# Sheet1.net
KiCad netlist of a schematic drawn in Altium Designer
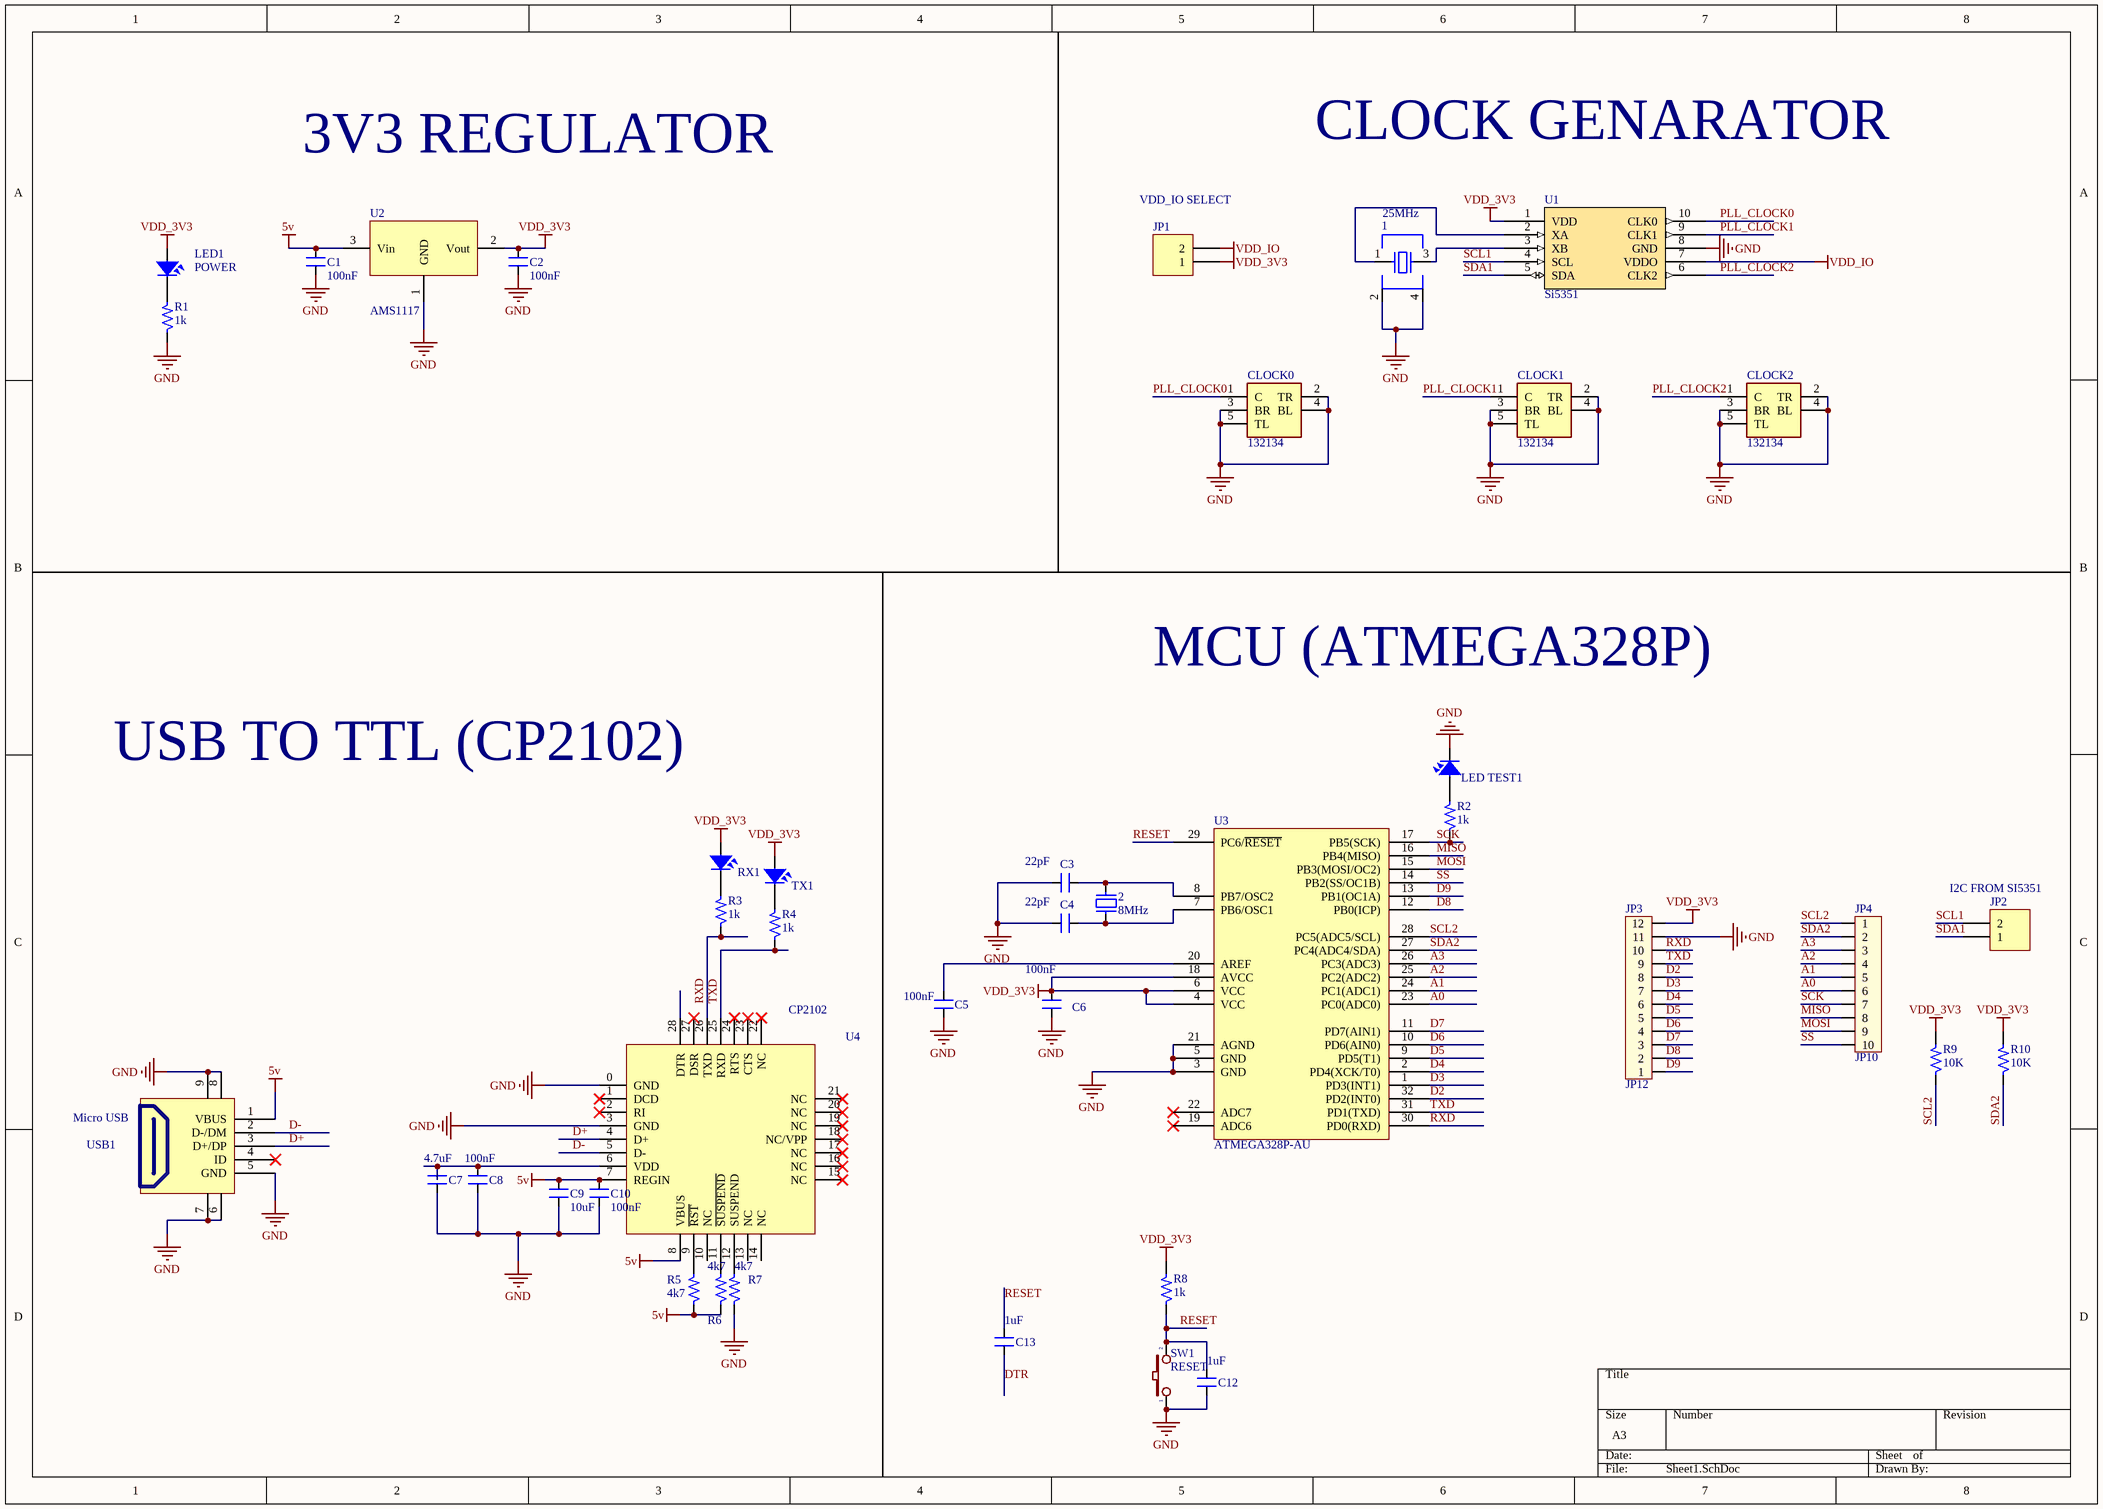
[diagram p0: Sheet1.SchDoc]

(export (version "E")
  (design (tool "Eeschema 10.0.6"))
  (components
    (comp (ref "1")
      (value "25MHz")
      (footprint "XT4-3.2x2.5")
      (description "4 pin crystal surface mount")
      (libsource (lib "HaiThai") (part "XT4_SMD"))
    )
    (comp (ref "2")
      (value "8MHz")
      (footprint "XT 5032")
      (description "Crystal 455kHz Infrared")
      (libsource (lib "HaiThai") (part "XT455k"))
    )
    (comp (ref "C1")
      (value "100nF")
      (footprint "0603_cap")
      (description "Cap np W0.4")
      (libsource (lib "HaiThai") (part "CN4"))
    )
    (comp (ref "C2")
      (value "100nF")
      (footprint "0603_cap")
      (description "Cap np W0.4")
      (libsource (lib "HaiThai") (part "CN4"))
    )
    (comp (ref "C3")
      (value "22pF")
      (footprint "0603_cap")
      (description "Cap np W0.4")
      (libsource (lib "HaiThai") (part "CN4"))
    )
    (comp (ref "C4")
      (value "22pF")
      (footprint "0603_cap")
      (description "Cap np W0.4")
      (libsource (lib "HaiThai") (part "CN4"))
    )
    (comp (ref "C5")
      (value "100nF")
      (footprint "0603_cap")
      (description "Cap np W0.4")
      (libsource (lib "HaiThai") (part "CN4"))
    )
    (comp (ref "C6")
      (value "100nF")
      (footprint "0603_cap")
      (description "Cap np W0.4")
      (libsource (lib "HaiThai") (part "CN4"))
    )
    (comp (ref "C7")
      (value "100nF")
      (footprint "0603_cap")
      (description "Cap np W0.4")
      (libsource (lib "HaiThai") (part "CN4"))
    )
    (comp (ref "C8")
      (value "4.7uF")
      (footprint "0603_cap")
      (description "Cap np W0.4")
      (libsource (lib "HaiThai") (part "CN4"))
    )
    (comp (ref "C9")
      (value "10uF")
      (footprint "0603_cap")
      (description "Cap np W0.4")
      (libsource (lib "HaiThai") (part "CN4"))
    )
    (comp (ref "C10")
      (value "100nF")
      (footprint "0603_cap")
      (description "Cap np W0.4")
      (libsource (lib "HaiThai") (part "CN4"))
    )
    (comp (ref "C12")
      (value "1uF")
      (footprint "0603_cap")
      (description "Cap np W0.4")
      (libsource (lib "HaiThai") (part "CN4"))
    )
    (comp (ref "C13")
      (value "1uF")
      (footprint "0603_cap")
      (description "Cap np W0.4")
      (libsource (lib "HaiThai") (part "CN4"))
    )
    (comp (ref "CLOCK0")
      (value "132134")
      (footprint "SMA-132322")
      (description "SMA Connector - STRAIGHT JACK FOR P.C. BOARD - Female")
      (libsource (lib "HaiThai") (part "132134"))
    )
    (comp (ref "CLOCK1")
      (value "132134")
      (footprint "SMA-132322")
      (description "SMA Connector - STRAIGHT JACK FOR P.C. BOARD - Female")
      (libsource (lib "HaiThai") (part "132134"))
    )
    (comp (ref "CLOCK2")
      (value "132134")
      (footprint "SMA-132322")
      (description "SMA Connector - STRAIGHT JACK FOR P.C. BOARD - Female")
      (libsource (lib "HaiThai") (part "132134"))
    )
    (comp (ref "JP1")
      (value "Header 2")
      (footprint "JP2-D1T")
      (description "Header, 2-Pin")
      (fields (field (name "MANUFACTURER") "Generic Components"))
      (libsource (lib "") (part "Header 2_1"))
    )
    (comp (ref "JP2")
      (value "Header 2")
      (footprint "JP2-D1T")
      (description "Header, 2-Pin")
      (fields (field (name "MANUFACTURER") "Generic Components"))
      (libsource (lib "HaiThai") (part "Header 2"))
    )
    (comp (ref "JP3")
      (value "JP12")
      (footprint "JP12-D1T")
      (description "Connector 12")
      (libsource (lib "HaiThai") (part "Con12"))
    )
    (comp (ref "JP4")
      (value "JP10")
      (footprint "JP10-D1T")
      (description "Connector 10")
      (libsource (lib "HaiThai") (part "Con10"))
    )
    (comp (ref "LED TEST1")
      (value "LED SMD")
      (footprint "0603_LED")
      (libsource (lib "HaiThai") (part "LED-SMD-0603"))
    )
    (comp (ref "LED1")
      (value "POWER")
      (footprint "0603_LED")
      (libsource (lib "HaiThai") (part "LED-SMD-0603"))
    )
    (comp (ref "R1")
      (value "1k")
      (footprint "0603_res")
      (description "Resistor 1/4W")
      (libsource (lib "HaiThai") (part "R"))
    )
    (comp (ref "R2")
      (value "1k")
      (footprint "0603_res")
      (description "Resistor 1/4W")
      (libsource (lib "HaiThai") (part "R"))
    )
    (comp (ref "R3")
      (value "1k")
      (footprint "0603_res")
      (description "Resistor 1/4W")
      (libsource (lib "HaiThai") (part "R"))
    )
    (comp (ref "R4")
      (value "1k")
      (footprint "0603_res")
      (description "Resistor 1/4W")
      (libsource (lib "HaiThai") (part "R"))
    )
    (comp (ref "R5")
      (value "4k7")
      (footprint "0603_res")
      (description "Resistor 1/4W")
      (libsource (lib "HaiThai") (part "R"))
    )
    (comp (ref "R6")
      (value "4k7")
      (footprint "0603_res")
      (description "Resistor 1/4W")
      (libsource (lib "HaiThai") (part "R"))
    )
    (comp (ref "R7")
      (value "4k7")
      (footprint "0603_res")
      (description "Resistor 1/4W")
      (libsource (lib "HaiThai") (part "R"))
    )
    (comp (ref "R8")
      (value "1k")
      (footprint "0603_res")
      (description "Resistor 1/4W")
      (libsource (lib "HaiThai") (part "R"))
    )
    (comp (ref "R9")
      (value "10K")
      (footprint "0603_res")
      (description "Resistor 1/4W")
      (libsource (lib "HaiThai") (part "R"))
    )
    (comp (ref "R10")
      (value "10K")
      (footprint "0603_res")
      (description "Resistor 1/4W")
      (libsource (lib "HaiThai") (part "R"))
    )
    (comp (ref "RX1")
      (value "LED SMD")
      (footprint "0603_LED")
      (libsource (lib "HaiThai") (part "LED-SMD-0603"))
    )
    (comp (ref "SW1")
      (value "RESET")
      (footprint "SW-SMD")
      (description "Switch button 2 pin")
      (libsource (lib "HaiThai") (part "SW2"))
    )
    (comp (ref "TX1")
      (value "LED SMD")
      (footprint "0603_LED")
      (libsource (lib "HaiThai") (part "LED-SMD-0603"))
    )
    (comp (ref "U1")
      (value "Si5351")
      (footprint "MSOP10_L")
      (description "I2C-PROGRAMMABLE ANY-FREQUENCY CMOS CLOCK")
      (libsource (lib "HaiThai") (part "Si5351"))
    )
    (comp (ref "U2") (value "AMS1117") (footprint "SOT223_N") (libsource (lib "HaiThai") (part "AMS1117")))
    (comp (ref "U3")
      (value "ATMEGA328P-AU")
      (footprint "QFP7X7-G32/X.45N")
      (description "8-bit AVR Microcontrollers")
      (libsource (lib "HaiThai") (part "ATMEGA328P-AU"))
    )
    (comp (ref "U4")
      (value "CP2102")
      (footprint "QFN28 - 9")
      (description "SINGLE-CHIP USB-TO-UART BRIDGE")
      (libsource (lib "HaiThai") (part "CP2102"))
    )
    (comp (ref "USB1")
      (value "Micro USB")
      (footprint "MICROUSB - v2")
      (libsource (lib "HaiThai") (part "USB Micro"))
    )
  )
  (nets
    (net (code "1") (name "/A0") (class "Default")
      (node (ref "JP4") (pin "6") (pinfunction "6_6") (pintype "passive"))
      (node (ref "U3") (pin "23") (pinfunction "PC0(ADC0)_23") (pintype "passive"))
    )
    (net (code "2") (name "/A1") (class "Default")
      (node (ref "JP4") (pin "5") (pinfunction "5_5") (pintype "passive"))
      (node (ref "U3") (pin "24") (pinfunction "PC1(ADC1)_24") (pintype "passive"))
    )
    (net (code "3") (name "/A2") (class "Default")
      (node (ref "JP4") (pin "4") (pinfunction "4_4") (pintype "passive"))
      (node (ref "U3") (pin "25") (pinfunction "PC2(ADC2)_25") (pintype "passive"))
    )
    (net (code "4") (name "/A3") (class "Default")
      (node (ref "JP4") (pin "3") (pinfunction "3_3") (pintype "passive"))
      (node (ref "U3") (pin "26") (pinfunction "PC3(ADC3)_26") (pintype "passive"))
    )
    (net (code "5") (name "/D+") (class "Default")
      (node (ref "U4") (pin "4") (pinfunction "D+_4") (pintype "passive"))
      (node (ref "USB1") (pin "3") (pinfunction "D+/DP_3") (pintype "passive"))
    )
    (net (code "6") (name "/D-") (class "Default")
      (node (ref "U4") (pin "5") (pinfunction "D-_5") (pintype "passive"))
      (node (ref "USB1") (pin "2") (pinfunction "D-/DM_2") (pintype "passive"))
    )
    (net (code "7") (name "/D2") (class "Default")
      (node (ref "JP3") (pin "8") (pinfunction "8_8") (pintype "passive"))
      (node (ref "U3") (pin "32") (pinfunction "PD2(INT0)_32") (pintype "passive"))
    )
    (net (code "8") (name "/D3") (class "Default")
      (node (ref "JP3") (pin "7") (pinfunction "7_7") (pintype "passive"))
      (node (ref "U3") (pin "1") (pinfunction "PD3(INT1)_1") (pintype "passive"))
    )
    (net (code "9") (name "/D4") (class "Default")
      (node (ref "JP3") (pin "6") (pinfunction "6_6") (pintype "passive"))
      (node (ref "U3") (pin "2") (pinfunction "PD4(XCK/T0)_2") (pintype "passive"))
    )
    (net (code "10") (name "/D5") (class "Default")
      (node (ref "JP3") (pin "5") (pinfunction "5_5") (pintype "passive"))
      (node (ref "U3") (pin "9") (pinfunction "PD5(T1)_9") (pintype "passive"))
    )
    (net (code "11") (name "/D6") (class "Default")
      (node (ref "JP3") (pin "4") (pinfunction "4_4") (pintype "passive"))
      (node (ref "U3") (pin "10") (pinfunction "PD6(AIN0)_10") (pintype "passive"))
    )
    (net (code "12") (name "/D7") (class "Default")
      (node (ref "JP3") (pin "3") (pinfunction "3_3") (pintype "passive"))
      (node (ref "U3") (pin "11") (pinfunction "PD7(AIN1)_11") (pintype "passive"))
    )
    (net (code "13") (name "/D8") (class "Default")
      (node (ref "JP3") (pin "2") (pinfunction "2_2") (pintype "passive"))
      (node (ref "U3") (pin "12") (pinfunction "PB0(ICP)_12") (pintype "passive"))
    )
    (net (code "14") (name "/D9") (class "Default")
      (node (ref "JP3") (pin "1") (pinfunction "1_1") (pintype "passive"))
      (node (ref "U3") (pin "13") (pinfunction "PB1(OC1A)_13") (pintype "passive"))
    )
    (net (code "15") (name "/DTR") (class "Default")
      (node (ref "C13") (pin "1") (pinfunction "1_1") (pintype "passive"))
    )
    (net (code "16") (name "/MISO") (class "Default")
      (node (ref "JP4") (pin "8") (pinfunction "8_8") (pintype "passive"))
      (node (ref "U3") (pin "16") (pinfunction "PB4(MISO)_16") (pintype "passive"))
    )
    (net (code "17") (name "/MOSI") (class "Default")
      (node (ref "JP4") (pin "9") (pinfunction "9_9") (pintype "passive"))
      (node (ref "U3") (pin "15") (pinfunction "PB3(MOSI/OC2)_15") (pintype "passive"))
    )
    (net (code "18") (name "/PLL_CLOCK0") (class "Default")
      (node (ref "CLOCK0") (pin "1") (pinfunction "C_1") (pintype "passive"))
      (node (ref "U1") (pin "10") (pinfunction "CLK0_10") (pintype "output"))
    )
    (net (code "19") (name "/PLL_CLOCK1") (class "Default")
      (node (ref "CLOCK1") (pin "1") (pinfunction "C_1") (pintype "passive"))
      (node (ref "U1") (pin "9") (pinfunction "CLK1_9") (pintype "output"))
    )
    (net (code "20") (name "/PLL_CLOCK2") (class "Default")
      (node (ref "CLOCK2") (pin "1") (pinfunction "C_1") (pintype "passive"))
      (node (ref "U1") (pin "6") (pinfunction "CLK2_6") (pintype "output"))
    )
    (net (code "21") (name "/RESET") (class "Default")
      (node (ref "C12") (pin "2") (pinfunction "2_2") (pintype "passive"))
      (node (ref "C13") (pin "2") (pinfunction "2_2") (pintype "passive"))
      (node (ref "R8") (pin "1") (pinfunction "1_1") (pintype "passive"))
      (node (ref "SW1") (pin "2") (pinfunction "2_2") (pintype "passive"))
      (node (ref "U3") (pin "29") (pinfunction "PC6/~{RESET}_29") (pintype "passive"))
    )
    (net (code "22") (name "/RXD") (class "Default")
      (node (ref "JP3") (pin "10") (pinfunction "10_10") (pintype "passive"))
      (node (ref "R3") (pin "1") (pinfunction "1_1") (pintype "passive"))
      (node (ref "U3") (pin "30") (pinfunction "PD0(RXD)_30") (pintype "passive"))
      (node (ref "U4") (pin "26") (pinfunction "TXD_26") (pintype "passive"))
    )
    (net (code "23") (name "/SCK") (class "Default")
      (node (ref "JP4") (pin "7") (pinfunction "7_7") (pintype "passive"))
      (node (ref "R2") (pin "1") (pinfunction "1_1") (pintype "passive"))
      (node (ref "U3") (pin "17") (pinfunction "PB5(SCK)_17") (pintype "passive"))
    )
    (net (code "24") (name "/SCL1") (class "Default")
      (node (ref "JP2") (pin "2") (pinfunction "2_2") (pintype "passive"))
      (node (ref "U1") (pin "4") (pinfunction "SCL_4") (pintype "input"))
    )
    (net (code "25") (name "/SCL2") (class "Default")
      (node (ref "JP4") (pin "1") (pinfunction "1_1") (pintype "passive"))
      (node (ref "R9") (pin "1") (pinfunction "1_1") (pintype "passive"))
      (node (ref "U3") (pin "28") (pinfunction "PC5(ADC5/SCL)_28") (pintype "passive"))
    )
    (net (code "26") (name "/SDA1") (class "Default")
      (node (ref "JP2") (pin "1") (pinfunction "1_1") (pintype "passive"))
      (node (ref "U1") (pin "5") (pinfunction "SDA_5") (pintype "bidirectional"))
    )
    (net (code "27") (name "/SDA2") (class "Default")
      (node (ref "JP4") (pin "2") (pinfunction "2_2") (pintype "passive"))
      (node (ref "R10") (pin "1") (pinfunction "1_1") (pintype "passive"))
      (node (ref "U3") (pin "27") (pinfunction "PC4(ADC4/SDA)_27") (pintype "passive"))
    )
    (net (code "28") (name "/SS") (class "Default")
      (node (ref "JP4") (pin "10") (pinfunction "10_10") (pintype "passive"))
      (node (ref "U3") (pin "14") (pinfunction "PB2(SS/OC1B)_14") (pintype "passive"))
    )
    (net (code "29") (name "/TXD") (class "Default")
      (node (ref "JP3") (pin "9") (pinfunction "9_9") (pintype "passive"))
      (node (ref "R4") (pin "1") (pinfunction "1_1") (pintype "passive"))
      (node (ref "U3") (pin "31") (pinfunction "PD1(TXD)_31") (pintype "passive"))
      (node (ref "U4") (pin "25") (pinfunction "RXD_25") (pintype "passive"))
    )
    (net (code "30") (name "5v") (class "Default")
      (node (ref "C1") (pin "2") (pinfunction "2_2") (pintype "passive"))
      (node (ref "C10") (pin "2") (pinfunction "2_2") (pintype "passive"))
      (node (ref "C9") (pin "2") (pinfunction "2_2") (pintype "passive"))
      (node (ref "R5") (pin "1") (pinfunction "1_1") (pintype "passive"))
      (node (ref "R6") (pin "1") (pinfunction "1_1") (pintype "passive"))
      (node (ref "U2") (pin "3") (pinfunction "Vin_3") (pintype "passive"))
      (node (ref "U4") (pin "7") (pinfunction "REGIN_7") (pintype "passive"))
      (node (ref "U4") (pin "8") (pinfunction "VBUS_8") (pintype "passive"))
      (node (ref "USB1") (pin "1") (pinfunction "VBUS_1") (pintype "passive"))
    )
    (net (code "31") (name "GND") (class "Default")
      (node (ref "1") (pin "2") (pinfunction "2_2") (pintype "passive"))
      (node (ref "1") (pin "4") (pinfunction "4_4") (pintype "passive"))
      (node (ref "C1") (pin "1") (pinfunction "1_1") (pintype "passive"))
      (node (ref "C10") (pin "1") (pinfunction "1_1") (pintype "passive"))
      (node (ref "C12") (pin "1") (pinfunction "1_1") (pintype "passive"))
      (node (ref "C2") (pin "1") (pinfunction "1_1") (pintype "passive"))
      (node (ref "C3") (pin "2") (pinfunction "2_2") (pintype "passive"))
      (node (ref "C4") (pin "2") (pinfunction "2_2") (pintype "passive"))
      (node (ref "C5") (pin "1") (pinfunction "1_1") (pintype "passive"))
      (node (ref "C6") (pin "1") (pinfunction "1_1") (pintype "passive"))
      (node (ref "C7") (pin "2") (pinfunction "2_2") (pintype "passive"))
      (node (ref "C8") (pin "1") (pinfunction "1_1") (pintype "passive"))
      (node (ref "C9") (pin "1") (pinfunction "1_1") (pintype "passive"))
      (node (ref "CLOCK0") (pin "2") (pinfunction "TR_2") (pintype "passive"))
      (node (ref "CLOCK0") (pin "3") (pinfunction "BR_3") (pintype "passive"))
      (node (ref "CLOCK0") (pin "4") (pinfunction "BL_4") (pintype "passive"))
      (node (ref "CLOCK0") (pin "5") (pinfunction "TL_5") (pintype "passive"))
      (node (ref "CLOCK1") (pin "2") (pinfunction "TR_2") (pintype "passive"))
      (node (ref "CLOCK1") (pin "3") (pinfunction "BR_3") (pintype "passive"))
      (node (ref "CLOCK1") (pin "4") (pinfunction "BL_4") (pintype "passive"))
      (node (ref "CLOCK1") (pin "5") (pinfunction "TL_5") (pintype "passive"))
      (node (ref "CLOCK2") (pin "2") (pinfunction "TR_2") (pintype "passive"))
      (node (ref "CLOCK2") (pin "3") (pinfunction "BR_3") (pintype "passive"))
      (node (ref "CLOCK2") (pin "4") (pinfunction "BL_4") (pintype "passive"))
      (node (ref "CLOCK2") (pin "5") (pinfunction "TL_5") (pintype "passive"))
      (node (ref "JP3") (pin "11") (pinfunction "11_11") (pintype "passive"))
      (node (ref "LED TEST1") (pin "2") (pinfunction "2_2") (pintype "passive"))
      (node (ref "R1") (pin "1") (pinfunction "1_1") (pintype "passive"))
      (node (ref "R7") (pin "1") (pinfunction "1_1") (pintype "passive"))
      (node (ref "SW1") (pin "1") (pinfunction "1_1") (pintype "passive"))
      (node (ref "U1") (pin "8") (pinfunction "GND_8") (pintype "passive"))
      (node (ref "U2") (pin "1") (pinfunction "GND_1") (pintype "passive"))
      (node (ref "U3") (pin "21") (pinfunction "AGND_21") (pintype "passive"))
      (node (ref "U3") (pin "3") (pinfunction "GND_3") (pintype "passive"))
      (node (ref "U3") (pin "5") (pinfunction "GND_5") (pintype "passive"))
      (node (ref "U4") (pin "0") (pinfunction "GND_0") (pintype "passive"))
      (node (ref "U4") (pin "3") (pinfunction "GND_3") (pintype "passive"))
      (node (ref "USB1") (pin "5") (pinfunction "GND_5") (pintype "passive"))
      (node (ref "USB1") (pin "6") (pinfunction "SH_6") (pintype "passive"))
      (node (ref "USB1") (pin "7") (pinfunction "SH_7") (pintype "passive"))
      (node (ref "USB1") (pin "8") (pinfunction "SH_8") (pintype "passive"))
      (node (ref "USB1") (pin "9") (pinfunction "SH_9") (pintype "passive"))
    )
    (net (code "32") (name "Net-(LED TEST1-Pad1)") (class "Default")
      (node (ref "LED TEST1") (pin "1") (pinfunction "1_1") (pintype "passive"))
      (node (ref "R2") (pin "2") (pinfunction "2_2") (pintype "passive"))
    )
    (net (code "33") (name "Net-(LED1-Pad2)") (class "Default")
      (node (ref "LED1") (pin "2") (pinfunction "2_2") (pintype "passive"))
      (node (ref "R1") (pin "2") (pinfunction "2_2") (pintype "passive"))
    )
    (net (code "34") (name "Net-(R3-Pad2)") (class "Default")
      (node (ref "R3") (pin "2") (pinfunction "2_2") (pintype "passive"))
      (node (ref "RX1") (pin "2") (pinfunction "2_2") (pintype "passive"))
    )
    (net (code "35") (name "Net-(R4-Pad2)") (class "Default")
      (node (ref "R4") (pin "2") (pinfunction "2_2") (pintype "passive"))
      (node (ref "TX1") (pin "2") (pinfunction "2_2") (pintype "passive"))
    )
    (net (code "36") (name "Net-(U1-XA)") (class "Default")
      (node (ref "1") (pin "1") (pinfunction "1_1") (pintype "passive"))
      (node (ref "U1") (pin "2") (pinfunction "XA_2") (pintype "input"))
    )
    (net (code "37") (name "Net-(U1-XB)") (class "Default")
      (node (ref "1") (pin "3") (pinfunction "3_3") (pintype "passive"))
      (node (ref "U1") (pin "3") (pinfunction "XB_3") (pintype "input"))
    )
    (net (code "38") (name "Net-(U3-AREF)") (class "Default")
      (node (ref "C5") (pin "2") (pinfunction "2_2") (pintype "passive"))
      (node (ref "U3") (pin "20") (pinfunction "AREF_20") (pintype "passive"))
    )
    (net (code "39") (name "Net-(U3-PB6{slash}OSC1)") (class "Default")
      (node (ref "2") (pin "1") (pinfunction "1_1") (pintype "passive"))
      (node (ref "C4") (pin "1") (pinfunction "1_1") (pintype "passive"))
      (node (ref "U3") (pin "7") (pinfunction "PB6/OSC1_7") (pintype "passive"))
    )
    (net (code "40") (name "Net-(U3-PB7{slash}OSC2)") (class "Default")
      (node (ref "2") (pin "2") (pinfunction "2_2") (pintype "passive"))
      (node (ref "C3") (pin "1") (pinfunction "1_1") (pintype "passive"))
      (node (ref "U3") (pin "8") (pinfunction "PB7/OSC2_8") (pintype "passive"))
    )
    (net (code "41") (name "Net-(U4-SUSPEND)") (class "Default")
      (node (ref "R7") (pin "2") (pinfunction "2_2") (pintype "passive"))
      (node (ref "U4") (pin "12") (pinfunction "SUSPEND_12") (pintype "passive"))
    )
    (net (code "42") (name "Net-(U4-VDD)") (class "Default")
      (node (ref "C7") (pin "1") (pinfunction "1_1") (pintype "passive"))
      (node (ref "C8") (pin "2") (pinfunction "2_2") (pintype "passive"))
      (node (ref "U4") (pin "6") (pinfunction "VDD_6") (pintype "passive"))
    )
    (net (code "43") (name "Net-(U4-~{RST})") (class "Default")
      (node (ref "R5") (pin "2") (pinfunction "2_2") (pintype "passive"))
      (node (ref "U4") (pin "9") (pinfunction "~{RST}_9") (pintype "passive"))
    )
    (net (code "44") (name "Net-(U4-~{SUSPEND})") (class "Default")
      (node (ref "R6") (pin "2") (pinfunction "2_2") (pintype "passive"))
      (node (ref "U4") (pin "11") (pinfunction "~{SUSPEND}_11") (pintype "passive"))
    )
    (net (code "45") (name "VDD_3V3") (class "Default")
      (node (ref "C2") (pin "2") (pinfunction "2_2") (pintype "passive"))
      (node (ref "C6") (pin "2") (pinfunction "2_2") (pintype "passive"))
      (node (ref "JP1") (pin "1") (pinfunction "1_1") (pintype "passive"))
      (node (ref "JP3") (pin "12") (pinfunction "12_12") (pintype "passive"))
      (node (ref "LED1") (pin "1") (pinfunction "1_1") (pintype "passive"))
      (node (ref "R10") (pin "2") (pinfunction "2_2") (pintype "passive"))
      (node (ref "R8") (pin "2") (pinfunction "2_2") (pintype "passive"))
      (node (ref "R9") (pin "2") (pinfunction "2_2") (pintype "passive"))
      (node (ref "RX1") (pin "1") (pinfunction "1_1") (pintype "passive"))
      (node (ref "TX1") (pin "1") (pinfunction "1_1") (pintype "passive"))
      (node (ref "U1") (pin "1") (pinfunction "VDD_1") (pintype "power_in"))
      (node (ref "U2") (pin "2") (pinfunction "Vout_2") (pintype "passive"))
      (node (ref "U3") (pin "18") (pinfunction "AVCC_18") (pintype "passive"))
      (node (ref "U3") (pin "4") (pinfunction "VCC_4") (pintype "passive"))
      (node (ref "U3") (pin "6") (pinfunction "VCC_6") (pintype "passive"))
    )
    (net (code "46") (name "VDD_IO") (class "Default")
      (node (ref "JP1") (pin "2") (pinfunction "2_2") (pintype "passive"))
      (node (ref "U1") (pin "7") (pinfunction "VDDO_7") (pintype "power_in"))
    )
    (net (code "47") (name "unconnected-(U3-ADC6-Pad19)") (class "Default")
      (node (ref "U3") (pin "19") (pinfunction "ADC6_19") (pintype "passive+no_connect"))
    )
    (net (code "48") (name "unconnected-(U3-ADC7-Pad22)") (class "Default")
      (node (ref "U3") (pin "22") (pinfunction "ADC7_22") (pintype "passive+no_connect"))
    )
    (net (code "49") (name "unconnected-(U4-CTS-Pad23)") (class "Default")
      (node (ref "U4") (pin "23") (pinfunction "CTS_23") (pintype "passive+no_connect"))
    )
    (net (code "50") (name "unconnected-(U4-DCD-Pad1)") (class "Default")
      (node (ref "U4") (pin "1") (pinfunction "DCD_1") (pintype "passive+no_connect"))
    )
    (net (code "51") (name "unconnected-(U4-DSR-Pad27)") (class "Default")
      (node (ref "U4") (pin "27") (pinfunction "DSR_27") (pintype "passive+no_connect"))
    )
    (net (code "52") (name "unconnected-(U4-DTR-Pad28)") (class "Default")
      (node (ref "U4") (pin "28") (pinfunction "DTR_28") (pintype "passive"))
    )
    (net (code "53") (name "unconnected-(U4-NC-Pad10)") (class "Default")
      (node (ref "U4") (pin "10") (pinfunction "NC_10") (pintype "passive"))
    )
    (net (code "54") (name "unconnected-(U4-NC-Pad13)") (class "Default")
      (node (ref "U4") (pin "13") (pinfunction "NC_13") (pintype "passive"))
    )
    (net (code "55") (name "unconnected-(U4-NC-Pad14)") (class "Default")
      (node (ref "U4") (pin "14") (pinfunction "NC_14") (pintype "passive"))
    )
    (net (code "56") (name "unconnected-(U4-NC-Pad15)") (class "Default")
      (node (ref "U4") (pin "15") (pinfunction "NC_15") (pintype "passive+no_connect"))
    )
    (net (code "57") (name "unconnected-(U4-NC-Pad16)") (class "Default")
      (node (ref "U4") (pin "16") (pinfunction "NC_16") (pintype "passive+no_connect"))
    )
    (net (code "58") (name "unconnected-(U4-NC-Pad17)") (class "Default")
      (node (ref "U4") (pin "17") (pinfunction "NC_17") (pintype "passive+no_connect"))
    )
    (net (code "59") (name "unconnected-(U4-NC-Pad19)") (class "Default")
      (node (ref "U4") (pin "19") (pinfunction "NC_19") (pintype "passive+no_connect"))
    )
    (net (code "60") (name "unconnected-(U4-NC-Pad20)") (class "Default")
      (node (ref "U4") (pin "20") (pinfunction "NC_20") (pintype "passive+no_connect"))
    )
    (net (code "61") (name "unconnected-(U4-NC-Pad21)") (class "Default")
      (node (ref "U4") (pin "21") (pinfunction "NC_21") (pintype "passive+no_connect"))
    )
    (net (code "62") (name "unconnected-(U4-NC-Pad22)") (class "Default")
      (node (ref "U4") (pin "22") (pinfunction "NC_22") (pintype "passive+no_connect"))
    )
    (net (code "63") (name "unconnected-(U4-NC{slash}VPP-Pad18)") (class "Default")
      (node (ref "U4") (pin "18") (pinfunction "NC/VPP_18") (pintype "passive+no_connect"))
    )
    (net (code "64") (name "unconnected-(U4-RI-Pad2)") (class "Default")
      (node (ref "U4") (pin "2") (pinfunction "RI_2") (pintype "passive+no_connect"))
    )
    (net (code "65") (name "unconnected-(U4-RTS-Pad24)") (class "Default")
      (node (ref "U4") (pin "24") (pinfunction "RTS_24") (pintype "passive+no_connect"))
    )
    (net (code "66") (name "unconnected-(USB1-ID-Pad4)") (class "Default")
      (node (ref "USB1") (pin "4") (pinfunction "ID_4") (pintype "passive+no_connect"))
    )
  )
)
